# IOb.net
KiCad netlist of a schematic drawn in Altium Designer
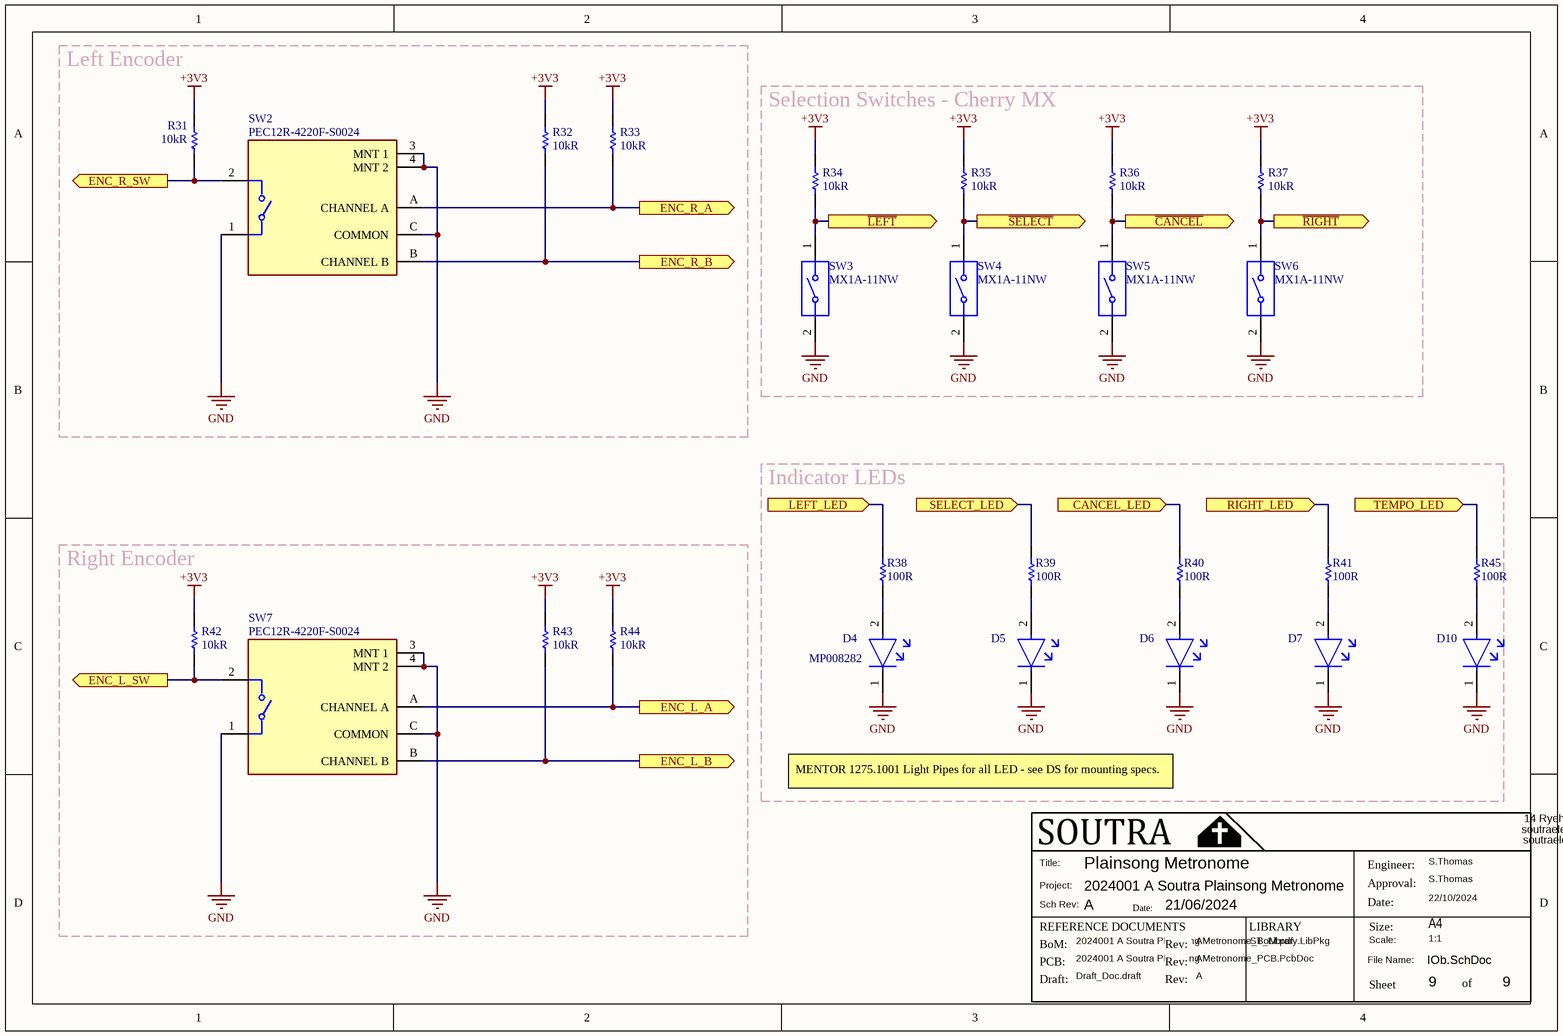
[diagram p0: IOb.SchDoc]

(export (version "E")
  (design (tool "Eeschema 10.0.6"))
  (components
    (comp (ref "D4")
      (value "MP008282")
      (footprint "DIOC_0603_1706X06L")
      (description "Led, Green, 70Mcd, 575Nm, 0603 Rohs Compliant: Yes")
      (fields (field (name "MANUFACTURER") "Multicomp") (field (name "ALTERNATIVE PART") "LG Q396-PS-35"))
      (libsource (lib "ST_Library") (part "MP008282"))
    )
    (comp (ref "D5")
      (value "MP008282")
      (footprint "DIOC_0603_1706X06L")
      (description "Led, Green, 70Mcd, 575Nm, 0603 Rohs Compliant: Yes")
      (fields (field (name "MANUFACTURER") "Multicomp") (field (name "ALTERNATIVE PART") "LG Q396-PS-35"))
      (libsource (lib "ST_Library") (part "MP008282"))
    )
    (comp (ref "D6")
      (value "MP008282")
      (footprint "DIOC_0603_1706X06L")
      (description "Led, Green, 70Mcd, 575Nm, 0603 Rohs Compliant: Yes")
      (fields (field (name "MANUFACTURER") "Multicomp") (field (name "ALTERNATIVE PART") "LG Q396-PS-35"))
      (libsource (lib "ST_Library") (part "MP008282"))
    )
    (comp (ref "D7")
      (value "MP008282")
      (footprint "DIOC_0603_1706X06L")
      (description "Led, Green, 70Mcd, 575Nm, 0603 Rohs Compliant: Yes")
      (fields (field (name "MANUFACTURER") "Multicomp") (field (name "ALTERNATIVE PART") "LG Q396-PS-35"))
      (libsource (lib "ST_Library") (part "MP008282"))
    )
    (comp (ref "D10")
      (value "MP008282")
      (footprint "DIOC_0603_1706X06L")
      (description "Led, Green, 70Mcd, 575Nm, 0603 Rohs Compliant: Yes")
      (fields (field (name "MANUFACTURER") "Multicomp") (field (name "ALTERNATIVE PART") "LG Q396-PS-35"))
      (libsource (lib "ST_Library") (part "MP008282"))
    )
    (comp (ref "R31")
      (value "10kR")
      (footprint "RESC_0805_2013X50X30LL20T20")
      (fields
        (field (name "MANUFACTURER") "Yageo")
        (field (name "MANUFACTURER PART NUMBER") "RC0805JR-0710KL")
        (field (name "TOLERANCE") "5%")
      )
      (libsource (lib "ST_Library") (part "RC0805JR-0710KL"))
    )
    (comp (ref "R32")
      (value "10kR")
      (footprint "RESC_0805_2013X50X30LL20T20")
      (fields
        (field (name "MANUFACTURER") "Yageo")
        (field (name "MANUFACTURER PART NUMBER") "RC0805JR-0710KL")
        (field (name "TOLERANCE") "5%")
      )
      (libsource (lib "ST_Library") (part "RC0805JR-0710KL"))
    )
    (comp (ref "R33")
      (value "10kR")
      (footprint "RESC_0805_2013X50X30LL20T20")
      (fields
        (field (name "MANUFACTURER") "Yageo")
        (field (name "MANUFACTURER PART NUMBER") "RC0805JR-0710KL")
        (field (name "TOLERANCE") "5%")
      )
      (libsource (lib "ST_Library") (part "RC0805JR-0710KL"))
    )
    (comp (ref "R34")
      (value "10kR")
      (footprint "RESC_0805_2013X50X30LL20T20")
      (fields
        (field (name "MANUFACTURER") "Yageo")
        (field (name "MANUFACTURER PART NUMBER") "RC0805JR-0710KL")
        (field (name "TOLERANCE") "5%")
      )
      (libsource (lib "ST_Library") (part "RC0805JR-0710KL"))
    )
    (comp (ref "R35")
      (value "10kR")
      (footprint "RESC_0805_2013X50X30LL20T20")
      (fields
        (field (name "MANUFACTURER") "Yageo")
        (field (name "MANUFACTURER PART NUMBER") "RC0805JR-0710KL")
        (field (name "TOLERANCE") "5%")
      )
      (libsource (lib "ST_Library") (part "RC0805JR-0710KL"))
    )
    (comp (ref "R36")
      (value "10kR")
      (footprint "RESC_0805_2013X50X30LL20T20")
      (fields
        (field (name "MANUFACTURER") "Yageo")
        (field (name "MANUFACTURER PART NUMBER") "RC0805JR-0710KL")
        (field (name "TOLERANCE") "5%")
      )
      (libsource (lib "ST_Library") (part "RC0805JR-0710KL"))
    )
    (comp (ref "R37")
      (value "10kR")
      (footprint "RESC_0805_2013X50X30LL20T20")
      (fields
        (field (name "MANUFACTURER") "Yageo")
        (field (name "MANUFACTURER PART NUMBER") "RC0805JR-0710KL")
        (field (name "TOLERANCE") "5%")
      )
      (libsource (lib "ST_Library") (part "RC0805JR-0710KL"))
    )
    (comp (ref "R38")
      (value "100R")
      (footprint "RESC_0805_2013X50X30LL20T20")
      (fields
        (field (name "MANUFACTURER") "Vishay Dale")
        (field (name "MANUFACTURER PART NUMBER") "CRCW0805100RFKTA")
        (field (name "TOLERANCE") "1%")
      )
      (libsource (lib "ST_Library") (part "CRCW0805100RFKTA"))
    )
    (comp (ref "R39")
      (value "100R")
      (footprint "RESC_0805_2013X50X30LL20T20")
      (fields
        (field (name "MANUFACTURER") "Vishay Dale")
        (field (name "MANUFACTURER PART NUMBER") "CRCW0805100RFKTA")
        (field (name "TOLERANCE") "1%")
      )
      (libsource (lib "ST_Library") (part "CRCW0805100RFKTA"))
    )
    (comp (ref "R40")
      (value "100R")
      (footprint "RESC_0805_2013X50X30LL20T20")
      (fields
        (field (name "MANUFACTURER") "Vishay Dale")
        (field (name "MANUFACTURER PART NUMBER") "CRCW0805100RFKTA")
        (field (name "TOLERANCE") "1%")
      )
      (libsource (lib "ST_Library") (part "CRCW0805100RFKTA"))
    )
    (comp (ref "R41")
      (value "100R")
      (footprint "RESC_0805_2013X50X30LL20T20")
      (fields
        (field (name "MANUFACTURER") "Vishay Dale")
        (field (name "MANUFACTURER PART NUMBER") "CRCW0805100RFKTA")
        (field (name "TOLERANCE") "1%")
      )
      (libsource (lib "ST_Library") (part "CRCW0805100RFKTA"))
    )
    (comp (ref "R42")
      (value "10kR")
      (footprint "RESC_0805_2013X50X30LL20T20")
      (fields
        (field (name "MANUFACTURER") "Yageo")
        (field (name "MANUFACTURER PART NUMBER") "RC0805JR-0710KL")
        (field (name "TOLERANCE") "5%")
      )
      (libsource (lib "ST_Library") (part "RC0805JR-0710KL"))
    )
    (comp (ref "R43")
      (value "10kR")
      (footprint "RESC_0805_2013X50X30LL20T20")
      (fields
        (field (name "MANUFACTURER") "Yageo")
        (field (name "MANUFACTURER PART NUMBER") "RC0805JR-0710KL")
        (field (name "TOLERANCE") "5%")
      )
      (libsource (lib "ST_Library") (part "RC0805JR-0710KL"))
    )
    (comp (ref "R44")
      (value "10kR")
      (footprint "RESC_0805_2013X50X30LL20T20")
      (fields
        (field (name "MANUFACTURER") "Yageo")
        (field (name "MANUFACTURER PART NUMBER") "RC0805JR-0710KL")
        (field (name "TOLERANCE") "5%")
      )
      (libsource (lib "ST_Library") (part "RC0805JR-0710KL"))
    )
    (comp (ref "R45")
      (value "100R")
      (footprint "RESC_0805_2013X50X30LL20T20")
      (fields
        (field (name "MANUFACTURER") "Vishay Dale")
        (field (name "MANUFACTURER PART NUMBER") "CRCW0805100RFKTA")
        (field (name "TOLERANCE") "1%")
      )
      (libsource (lib "ST_Library") (part "CRCW0805100RFKTA"))
    )
    (comp (ref "SW2")
      (value "PEC12R-4220F-S0024")
      (footprint "BOURNS_PEC12R-4220F-S0024")
      (description "Rotary Position Encoder, Single, 2 Channels")
      (fields (field (name "MANUFACTURER") "Bourns"))
      (libsource (lib "ST_Library") (part "PEC12R-4220F-S0024"))
    )
    (comp (ref "SW3")
      (value "MX1A-11NW")
      (footprint "CHERRY_MX1A-11NW")
      (fields (field (name "MANUFACTURER") "Cherry"))
      (libsource (lib "ST_Library") (part "MX1A-11NW"))
    )
    (comp (ref "SW4")
      (value "MX1A-11NW")
      (footprint "CHERRY_MX1A-11NW")
      (fields (field (name "MANUFACTURER") "Cherry"))
      (libsource (lib "ST_Library") (part "MX1A-11NW"))
    )
    (comp (ref "SW5")
      (value "MX1A-11NW")
      (footprint "CHERRY_MX1A-11NW")
      (fields (field (name "MANUFACTURER") "Cherry"))
      (libsource (lib "ST_Library") (part "MX1A-11NW"))
    )
    (comp (ref "SW6")
      (value "MX1A-11NW")
      (footprint "CHERRY_MX1A-11NW")
      (fields (field (name "MANUFACTURER") "Cherry"))
      (libsource (lib "ST_Library") (part "MX1A-11NW"))
    )
    (comp (ref "SW7")
      (value "PEC12R-4220F-S0024")
      (footprint "BOURNS_PEC12R-4220F-S0024")
      (description "Rotary Position Encoder, Single, 2 Channels")
      (fields (field (name "MANUFACTURER") "Bourns"))
      (libsource (lib "ST_Library") (part "PEC12R-4220F-S0024"))
    )
  )
  (nets
    (net (code "1") (name "+3V3") (class "Default")
      (node (ref "R31") (pin "2") (pinfunction "2_2") (pintype "passive"))
      (node (ref "R32") (pin "2") (pinfunction "2_2") (pintype "passive"))
      (node (ref "R33") (pin "2") (pinfunction "2_2") (pintype "passive"))
      (node (ref "R34") (pin "2") (pinfunction "2_2") (pintype "passive"))
      (node (ref "R35") (pin "2") (pinfunction "2_2") (pintype "passive"))
      (node (ref "R36") (pin "2") (pinfunction "2_2") (pintype "passive"))
      (node (ref "R37") (pin "2") (pinfunction "2_2") (pintype "passive"))
      (node (ref "R42") (pin "2") (pinfunction "2_2") (pintype "passive"))
      (node (ref "R43") (pin "2") (pinfunction "2_2") (pintype "passive"))
      (node (ref "R44") (pin "2") (pinfunction "2_2") (pintype "passive"))
    )
    (net (code "2") (name "/CANCEL_LED") (class "Default")
      (node (ref "R40") (pin "1") (pinfunction "1_1") (pintype "passive"))
    )
    (net (code "3") (name "/ENC_L_A") (class "Default")
      (node (ref "R44") (pin "1") (pinfunction "1_1") (pintype "passive"))
      (node (ref "SW7") (pin "A") (pinfunction "CHANNEL_A_A") (pintype "passive"))
    )
    (net (code "4") (name "/ENC_L_B") (class "Default")
      (node (ref "R43") (pin "1") (pinfunction "1_1") (pintype "passive"))
      (node (ref "SW7") (pin "B") (pinfunction "CHANNEL_B_B") (pintype "passive"))
    )
    (net (code "5") (name "/ENC_L_SW") (class "Default")
      (node (ref "R42") (pin "1") (pinfunction "1_1") (pintype "passive"))
      (node (ref "SW7") (pin "2") (pinfunction "2_2") (pintype "passive"))
    )
    (net (code "6") (name "/ENC_R_A") (class "Default")
      (node (ref "R33") (pin "1") (pinfunction "1_1") (pintype "passive"))
      (node (ref "SW2") (pin "A") (pinfunction "CHANNEL_A_A") (pintype "passive"))
    )
    (net (code "7") (name "/ENC_R_B") (class "Default")
      (node (ref "R32") (pin "1") (pinfunction "1_1") (pintype "passive"))
      (node (ref "SW2") (pin "B") (pinfunction "CHANNEL_B_B") (pintype "passive"))
    )
    (net (code "8") (name "/ENC_R_SW") (class "Default")
      (node (ref "R31") (pin "1") (pinfunction "1_1") (pintype "passive"))
      (node (ref "SW2") (pin "2") (pinfunction "2_2") (pintype "passive"))
    )
    (net (code "9") (name "/LEFT_LED") (class "Default")
      (node (ref "R38") (pin "1") (pinfunction "1_1") (pintype "passive"))
    )
    (net (code "10") (name "/RIGHT_LED") (class "Default")
      (node (ref "R41") (pin "1") (pinfunction "1_1") (pintype "passive"))
    )
    (net (code "11") (name "/SELECT_LED") (class "Default")
      (node (ref "R39") (pin "1") (pinfunction "1_1") (pintype "passive"))
    )
    (net (code "12") (name "/TEMPO_LED") (class "Default")
      (node (ref "R45") (pin "1") (pinfunction "1_1") (pintype "passive"))
    )
    (net (code "13") (name "/~{CANCEL}") (class "Default")
      (node (ref "R36") (pin "1") (pinfunction "1_1") (pintype "passive"))
      (node (ref "SW5") (pin "1") (pinfunction "1_1") (pintype "passive"))
    )
    (net (code "14") (name "/~{LEFT}") (class "Default")
      (node (ref "R34") (pin "1") (pinfunction "1_1") (pintype "passive"))
      (node (ref "SW3") (pin "1") (pinfunction "1_1") (pintype "passive"))
    )
    (net (code "15") (name "/~{RIGHT}") (class "Default")
      (node (ref "R37") (pin "1") (pinfunction "1_1") (pintype "passive"))
      (node (ref "SW6") (pin "1") (pinfunction "1_1") (pintype "passive"))
    )
    (net (code "16") (name "/~{SELECT}") (class "Default")
      (node (ref "R35") (pin "1") (pinfunction "1_1") (pintype "passive"))
      (node (ref "SW4") (pin "1") (pinfunction "1_1") (pintype "passive"))
    )
    (net (code "17") (name "GND") (class "Default")
      (node (ref "D10") (pin "1") (pinfunction "C_1") (pintype "passive"))
      (node (ref "D4") (pin "1") (pinfunction "C_1") (pintype "passive"))
      (node (ref "D5") (pin "1") (pinfunction "C_1") (pintype "passive"))
      (node (ref "D6") (pin "1") (pinfunction "C_1") (pintype "passive"))
      (node (ref "D7") (pin "1") (pinfunction "C_1") (pintype "passive"))
      (node (ref "SW2") (pin "1") (pinfunction "1_1") (pintype "passive"))
      (node (ref "SW2") (pin "3") (pinfunction "MNT_1_3") (pintype "passive"))
      (node (ref "SW2") (pin "4") (pinfunction "MNT_2_4") (pintype "passive"))
      (node (ref "SW2") (pin "C") (pinfunction "COMMON_C") (pintype "passive"))
      (node (ref "SW3") (pin "2") (pinfunction "2_2") (pintype "passive"))
      (node (ref "SW4") (pin "2") (pinfunction "2_2") (pintype "passive"))
      (node (ref "SW5") (pin "2") (pinfunction "2_2") (pintype "passive"))
      (node (ref "SW6") (pin "2") (pinfunction "2_2") (pintype "passive"))
      (node (ref "SW7") (pin "1") (pinfunction "1_1") (pintype "passive"))
      (node (ref "SW7") (pin "3") (pinfunction "MNT_1_3") (pintype "passive"))
      (node (ref "SW7") (pin "4") (pinfunction "MNT_2_4") (pintype "passive"))
      (node (ref "SW7") (pin "C") (pinfunction "COMMON_C") (pintype "passive"))
    )
    (net (code "18") (name "Net-(D4-A)") (class "Default")
      (node (ref "D4") (pin "2") (pinfunction "A_2") (pintype "passive"))
      (node (ref "R38") (pin "2") (pinfunction "2_2") (pintype "passive"))
    )
    (net (code "19") (name "Net-(D5-A)") (class "Default")
      (node (ref "D5") (pin "2") (pinfunction "A_2") (pintype "passive"))
      (node (ref "R39") (pin "2") (pinfunction "2_2") (pintype "passive"))
    )
    (net (code "20") (name "Net-(D6-A)") (class "Default")
      (node (ref "D6") (pin "2") (pinfunction "A_2") (pintype "passive"))
      (node (ref "R40") (pin "2") (pinfunction "2_2") (pintype "passive"))
    )
    (net (code "21") (name "Net-(D7-A)") (class "Default")
      (node (ref "D7") (pin "2") (pinfunction "A_2") (pintype "passive"))
      (node (ref "R41") (pin "2") (pinfunction "2_2") (pintype "passive"))
    )
    (net (code "22") (name "Net-(D10-A)") (class "Default")
      (node (ref "D10") (pin "2") (pinfunction "A_2") (pintype "passive"))
      (node (ref "R45") (pin "2") (pinfunction "2_2") (pintype "passive"))
    )
  )
)
